# Vaibhav_Data_logger.net
KiCad netlist of a schematic drawn in EAGLE
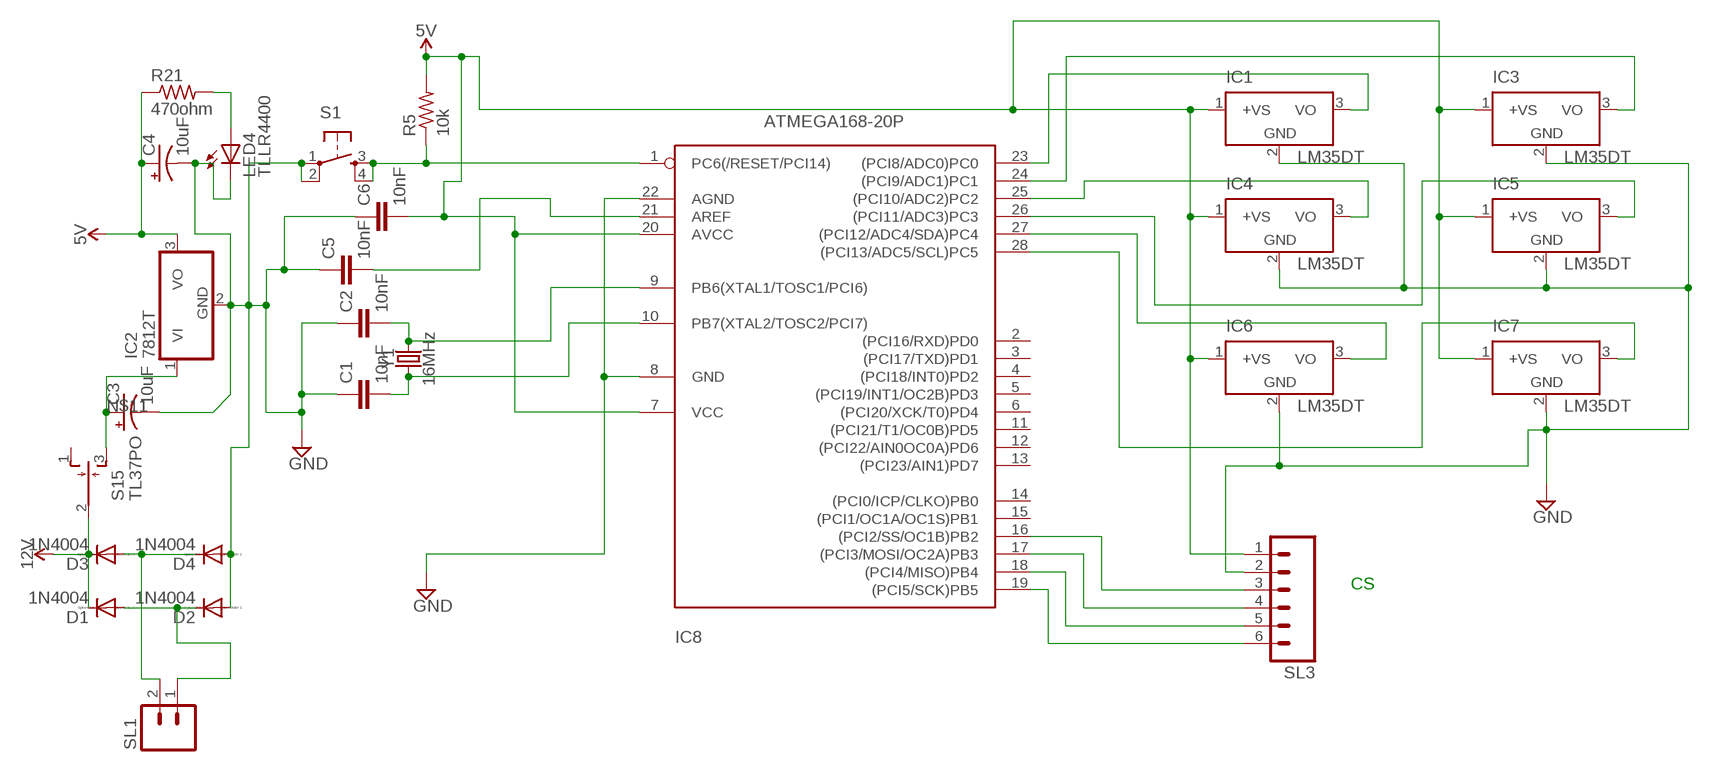
[diagram p0: schematic, sheet 1]

(export (version "E")
  (design (tool "Eeschema 10.0.6"))
  (components
    (comp (ref "C1")
      (value "10nF")
      (footprint "eagle-import:CAP-PTH-10MM")
      (libsource (lib "eagle-import") (part "10NF-PTH-10MM-10000V-1-%"))
    )
    (comp (ref "C2")
      (value "10nF")
      (footprint "eagle-import:CAP-PTH-10MM")
      (libsource (lib "eagle-import") (part "10NF-PTH-10MM-10000V-1-%"))
    )
    (comp (ref "C3")
      (value "10uF")
      (footprint "eagle-import:CPOL-RADIAL-2.5MM-5MM-KIT")
      (libsource (lib "eagle-import") (part "10UF-POLAR-RADIAL-2.5MM-KIT-25V-20%"))
    )
    (comp (ref "C4")
      (value "10uF")
      (footprint "eagle-import:CPOL-RADIAL-2.5MM-5MM-KIT")
      (libsource (lib "eagle-import") (part "10UF-POLAR-RADIAL-2.5MM-KIT-25V-20%"))
    )
    (comp (ref "C5")
      (value "10nF")
      (footprint "eagle-import:CAP-PTH-10MM")
      (libsource (lib "eagle-import") (part "10NF-PTH-10MM-10000V-1-%"))
    )
    (comp (ref "C6")
      (value "10nF")
      (footprint "eagle-import:CAP-PTH-10MM")
      (libsource (lib "eagle-import") (part "10NF-PTH-10MM-10000V-1-%"))
    )
    (comp (ref "D1")
      (value "1N4004")
      (footprint "eagle-import:DO41-10")
      (libsource (lib "eagle-import") (part "1N4004"))
    )
    (comp (ref "D2")
      (value "1N4004")
      (footprint "eagle-import:DO41-10")
      (libsource (lib "eagle-import") (part "1N4004"))
    )
    (comp (ref "D3")
      (value "1N4004")
      (footprint "eagle-import:DO41-10")
      (libsource (lib "eagle-import") (part "1N4004"))
    )
    (comp (ref "D4")
      (value "1N4004")
      (footprint "eagle-import:DO41-10")
      (libsource (lib "eagle-import") (part "1N4004"))
    )
    (comp (ref "IC1")
      (value "LM35DT")
      (footprint "eagle-import:TO220V")
      (libsource (lib "eagle-import") (part "LM35DT"))
    )
    (comp (ref "IC2")
      (value "7812T")
      (footprint "eagle-import:TO220H")
      (libsource (lib "eagle-import") (part "78T12"))
    )
    (comp (ref "IC3")
      (value "LM35DT")
      (footprint "eagle-import:TO220V")
      (libsource (lib "eagle-import") (part "LM35DT"))
    )
    (comp (ref "IC4")
      (value "LM35DT")
      (footprint "eagle-import:TO220V")
      (libsource (lib "eagle-import") (part "LM35DT"))
    )
    (comp (ref "IC5")
      (value "LM35DT")
      (footprint "eagle-import:TO220V")
      (libsource (lib "eagle-import") (part "LM35DT"))
    )
    (comp (ref "IC6")
      (value "LM35DT")
      (footprint "eagle-import:TO220V")
      (libsource (lib "eagle-import") (part "LM35DT"))
    )
    (comp (ref "IC7")
      (value "LM35DT")
      (footprint "eagle-import:TO220V")
      (libsource (lib "eagle-import") (part "LM35DT"))
    )
    (comp (ref "IC8")
      (value "ATMEGA168-20P")
      (footprint "eagle-import:DIL28-3")
      (libsource (lib "eagle-import") (part "ATMEGA168P-20"))
    )
    (comp (ref "LED4")
      (value "TLLR4400")
      (footprint "eagle-import:LED3MM")
      (fields (field (name "MF") "VISHAY SEMICONDUCTOR"))
      (libsource (lib "eagle-import") (part "TLLR4400"))
    )
    (comp (ref "R5")
      (value "10k")
      (footprint "eagle-import:0207_12")
      (libsource (lib "eagle-import") (part "R-US_0207/12"))
    )
    (comp (ref "R21")
      (value "470ohm")
      (footprint "eagle-import:0207_12")
      (libsource (lib "eagle-import") (part "R-US_0207/12"))
    )
    (comp (ref "S1")
      (value "TAC_SWITCHPTH")
      (footprint "eagle-import:TACTILE-PTH")
      (libsource (lib "eagle-import") (part "TAC_SWITCHPTH"))
    )
    (comp (ref "S15")
      (value "TL37PO")
      (footprint "eagle-import:TL3XPO")
      (libsource (lib "eagle-import") (part "TL37PO"))
    )
    (comp (ref "SL1")
      (value "MA02")
      (footprint "eagle-import:02PA")
      (libsource (lib "eagle-import") (part "MA02"))
    )
    (comp (ref "SL3")
      (value "MA06")
      (footprint "eagle-import:06PA")
      (libsource (lib "eagle-import") (part "MA06"))
    )
    (comp (ref "Y1")
      (value "16MHz")
      (footprint "eagle-import:HC49US")
      (libsource (lib "eagle-import") (part "CRYSTAL-16MHZPTH-HC49US"))
    )
  )
  (nets
    (net (code "1") (name "/N$11") (class "Default")
      (node (ref "C3") (pin "1") (pinfunction "+_1") (pintype "passive"))
      (node (ref "IC2") (pin "1") (pinfunction "VI_1") (pintype "input"))
      (node (ref "S15") (pin "3") (pinfunction "S_3") (pintype "passive"))
    )
    (net (code "2") (name "5V") (class "Default")
      (node (ref "C4") (pin "1") (pinfunction "+_1") (pintype "passive"))
      (node (ref "C6") (pin "2") (pinfunction "2_2") (pintype "passive"))
      (node (ref "IC1") (pin "1") (pinfunction "+VS_1") (pintype "input"))
      (node (ref "IC2") (pin "3") (pinfunction "VO_3") (pintype "passive"))
      (node (ref "IC3") (pin "1") (pinfunction "+VS_1") (pintype "input"))
      (node (ref "IC4") (pin "1") (pinfunction "+VS_1") (pintype "input"))
      (node (ref "IC5") (pin "1") (pinfunction "+VS_1") (pintype "input"))
      (node (ref "IC6") (pin "1") (pinfunction "+VS_1") (pintype "input"))
      (node (ref "IC7") (pin "1") (pinfunction "+VS_1") (pintype "input"))
      (node (ref "IC8") (pin "20") (pinfunction "AVCC_20") (pintype "bidirectional"))
      (node (ref "IC8") (pin "7") (pinfunction "VCC_7") (pintype "bidirectional"))
      (node (ref "R21") (pin "1") (pinfunction "1_1") (pintype "passive"))
      (node (ref "R5") (pin "2") (pinfunction "2_2") (pintype "passive"))
      (node (ref "SL3") (pin "1") (pinfunction "1_1") (pintype "passive"))
    )
    (net (code "3") (name "12V") (class "Default")
      (node (ref "D1") (pin "C") (pinfunction "C_C") (pintype "passive"))
      (node (ref "D3") (pin "C") (pinfunction "C_C") (pintype "passive"))
      (node (ref "S15") (pin "2") (pinfunction "P_2") (pintype "passive"))
    )
    (net (code "4") (name "GND") (class "Default")
      (node (ref "C1") (pin "1") (pinfunction "1_1") (pintype "passive"))
      (node (ref "C2") (pin "1") (pinfunction "1_1") (pintype "passive"))
      (node (ref "C3") (pin "2") (pinfunction "-_2") (pintype "passive"))
      (node (ref "C4") (pin "2") (pinfunction "-_2") (pintype "passive"))
      (node (ref "C5") (pin "1") (pinfunction "1_1") (pintype "passive"))
      (node (ref "C6") (pin "1") (pinfunction "1_1") (pintype "passive"))
      (node (ref "D2") (pin "A") (pinfunction "A_A") (pintype "passive"))
      (node (ref "D4") (pin "A") (pinfunction "A_A") (pintype "passive"))
      (node (ref "IC1") (pin "2") (pinfunction "GND_2") (pintype "power_in"))
      (node (ref "IC2") (pin "2") (pinfunction "GND_2") (pintype "passive"))
      (node (ref "IC3") (pin "2") (pinfunction "GND_2") (pintype "power_in"))
      (node (ref "IC4") (pin "2") (pinfunction "GND_2") (pintype "power_in"))
      (node (ref "IC5") (pin "2") (pinfunction "GND_2") (pintype "power_in"))
      (node (ref "IC6") (pin "2") (pinfunction "GND_2") (pintype "power_in"))
      (node (ref "IC7") (pin "2") (pinfunction "GND_2") (pintype "power_in"))
      (node (ref "IC8") (pin "22") (pinfunction "AGND_22") (pintype "bidirectional"))
      (node (ref "IC8") (pin "8") (pinfunction "GND_8") (pintype "bidirectional"))
      (node (ref "LED4") (pin "K") (pinfunction "C_K") (pintype "passive"))
      (node (ref "S1") (pin "1") (pinfunction "1_1") (pintype "passive"))
      (node (ref "S1") (pin "2") (pinfunction "2_2") (pintype "passive"))
      (node (ref "SL3") (pin "2") (pinfunction "2_2") (pintype "passive"))
    )
    (net (code "5") (name "Net-(D1-PadA)") (class "Default")
      (node (ref "D1") (pin "A") (pinfunction "A_A") (pintype "passive"))
      (node (ref "D2") (pin "C") (pinfunction "C_C") (pintype "passive"))
      (node (ref "SL1") (pin "1") (pinfunction "1_1") (pintype "passive"))
    )
    (net (code "6") (name "Net-(D3-PadA)") (class "Default")
      (node (ref "D3") (pin "A") (pinfunction "A_A") (pintype "passive"))
      (node (ref "D4") (pin "C") (pinfunction "C_C") (pintype "passive"))
      (node (ref "SL1") (pin "2") (pinfunction "2_2") (pintype "passive"))
    )
    (net (code "7") (name "Net-(IC1-VO)") (class "Default")
      (node (ref "IC1") (pin "3") (pinfunction "VO_3") (pintype "input"))
      (node (ref "IC8") (pin "23") (pinfunction "(PCI8/ADC0)PC0_23") (pintype "bidirectional"))
    )
    (net (code "8") (name "Net-(IC3-VO)") (class "Default")
      (node (ref "IC3") (pin "3") (pinfunction "VO_3") (pintype "input"))
      (node (ref "IC8") (pin "24") (pinfunction "(PCI9/ADC1)PC1_24") (pintype "bidirectional"))
    )
    (net (code "9") (name "Net-(IC4-VO)") (class "Default")
      (node (ref "IC4") (pin "3") (pinfunction "VO_3") (pintype "input"))
      (node (ref "IC8") (pin "25") (pinfunction "(PCI10/ADC2)PC2_25") (pintype "bidirectional"))
    )
    (net (code "10") (name "Net-(IC5-VO)") (class "Default")
      (node (ref "IC5") (pin "3") (pinfunction "VO_3") (pintype "input"))
      (node (ref "IC8") (pin "26") (pinfunction "(PCI11/ADC3)PC3_26") (pintype "bidirectional"))
    )
    (net (code "11") (name "Net-(IC6-VO)") (class "Default")
      (node (ref "IC6") (pin "3") (pinfunction "VO_3") (pintype "input"))
      (node (ref "IC8") (pin "27") (pinfunction "(PCI12/ADC4/SDA)PC4_27") (pintype "bidirectional"))
    )
    (net (code "12") (name "Net-(IC7-VO)") (class "Default")
      (node (ref "IC7") (pin "3") (pinfunction "VO_3") (pintype "input"))
      (node (ref "IC8") (pin "28") (pinfunction "(PCI13/ADC5/SCL)PC5_28") (pintype "bidirectional"))
    )
    (net (code "13") (name "Net-(IC8-(PCI2{slash}SS{slash}OC1B)PB2)") (class "Default")
      (node (ref "IC8") (pin "16") (pinfunction "(PCI2/SS/OC1B)PB2_16") (pintype "bidirectional"))
      (node (ref "SL3") (pin "3") (pinfunction "3_3") (pintype "passive"))
    )
    (net (code "14") (name "Net-(IC8-(PCI3{slash}MOSI{slash}OC2A)PB3)") (class "Default")
      (node (ref "IC8") (pin "17") (pinfunction "(PCI3/MOSI/OC2A)PB3_17") (pintype "bidirectional"))
      (node (ref "SL3") (pin "4") (pinfunction "4_4") (pintype "passive"))
    )
    (net (code "15") (name "Net-(IC8-(PCI4{slash}MISO)PB4)") (class "Default")
      (node (ref "IC8") (pin "18") (pinfunction "(PCI4/MISO)PB4_18") (pintype "bidirectional"))
      (node (ref "SL3") (pin "5") (pinfunction "5_5") (pintype "passive"))
    )
    (net (code "16") (name "Net-(IC8-(PCI5{slash}SCK)PB5)") (class "Default")
      (node (ref "IC8") (pin "19") (pinfunction "(PCI5/SCK)PB5_19") (pintype "bidirectional"))
      (node (ref "SL3") (pin "6") (pinfunction "6_6") (pintype "passive"))
    )
    (net (code "17") (name "Net-(IC8-AREF)") (class "Default")
      (node (ref "C5") (pin "2") (pinfunction "2_2") (pintype "passive"))
      (node (ref "IC8") (pin "21") (pinfunction "AREF_21") (pintype "bidirectional"))
    )
    (net (code "18") (name "Net-(IC8-PB6(XTAL1{slash}TOSC1{slash}PCI6))") (class "Default")
      (node (ref "C2") (pin "2") (pinfunction "2_2") (pintype "passive"))
      (node (ref "IC8") (pin "9") (pinfunction "PB6(XTAL1/TOSC1/PCI6)_9") (pintype "bidirectional"))
      (node (ref "Y1") (pin "2") (pinfunction "2_2") (pintype "passive"))
    )
    (net (code "19") (name "Net-(IC8-PB7(XTAL2{slash}TOSC2{slash}PCI7))") (class "Default")
      (node (ref "C1") (pin "2") (pinfunction "2_2") (pintype "passive"))
      (node (ref "IC8") (pin "10") (pinfunction "PB7(XTAL2/TOSC2/PCI7)_10") (pintype "bidirectional"))
      (node (ref "Y1") (pin "1") (pinfunction "1_1") (pintype "passive"))
    )
    (net (code "20") (name "Net-(IC8-PC6({slash}RESET{slash}PCI14))") (class "Default")
      (node (ref "IC8") (pin "1") (pinfunction "PC6(/RESET/PCI14)_1") (pintype "bidirectional"))
      (node (ref "R5") (pin "1") (pinfunction "1_1") (pintype "passive"))
      (node (ref "S1") (pin "3") (pinfunction "3_3") (pintype "passive"))
      (node (ref "S1") (pin "4") (pinfunction "4_4") (pintype "passive"))
    )
    (net (code "21") (name "Net-(LED4-PadA)") (class "Default")
      (node (ref "LED4") (pin "A") (pinfunction "A_A") (pintype "passive"))
      (node (ref "R21") (pin "2") (pinfunction "2_2") (pintype "passive"))
    )
    (net (code "22") (name "unconnected-(IC8-(PCI0{slash}ICP{slash}CLKO)PB0-Pad14)") (class "Default")
      (node (ref "IC8") (pin "14") (pinfunction "(PCI0/ICP/CLKO)PB0_14") (pintype "bidirectional"))
    )
    (net (code "23") (name "unconnected-(IC8-(PCI1{slash}OC1A{slash}OC1S)PB1-Pad15)") (class "Default")
      (node (ref "IC8") (pin "15") (pinfunction "(PCI1/OC1A/OC1S)PB1_15") (pintype "bidirectional"))
    )
    (net (code "24") (name "unconnected-(IC8-(PCI16{slash}RXD)PD0-Pad2)") (class "Default")
      (node (ref "IC8") (pin "2") (pinfunction "(PCI16/RXD)PD0_2") (pintype "bidirectional"))
    )
    (net (code "25") (name "unconnected-(IC8-(PCI17{slash}TXD)PD1-Pad3)") (class "Default")
      (node (ref "IC8") (pin "3") (pinfunction "(PCI17/TXD)PD1_3") (pintype "bidirectional"))
    )
    (net (code "26") (name "unconnected-(IC8-(PCI18{slash}INT0)PD2-Pad4)") (class "Default")
      (node (ref "IC8") (pin "4") (pinfunction "(PCI18/INT0)PD2_4") (pintype "bidirectional"))
    )
    (net (code "27") (name "unconnected-(IC8-(PCI19{slash}INT1{slash}OC2B)PD3-Pad5)") (class "Default")
      (node (ref "IC8") (pin "5") (pinfunction "(PCI19/INT1/OC2B)PD3_5") (pintype "bidirectional"))
    )
    (net (code "28") (name "unconnected-(IC8-(PCI20{slash}XCK{slash}T0)PD4-Pad6)") (class "Default")
      (node (ref "IC8") (pin "6") (pinfunction "(PCI20/XCK/T0)PD4_6") (pintype "bidirectional"))
    )
    (net (code "29") (name "unconnected-(IC8-(PCI21{slash}T1{slash}OC0B)PD5-Pad11)") (class "Default")
      (node (ref "IC8") (pin "11") (pinfunction "(PCI21/T1/OC0B)PD5_11") (pintype "bidirectional"))
    )
    (net (code "30") (name "unconnected-(IC8-(PCI22{slash}AIN0OC0A)PD6-Pad12)") (class "Default")
      (node (ref "IC8") (pin "12") (pinfunction "(PCI22/AIN0OC0A)PD6_12") (pintype "bidirectional"))
    )
    (net (code "31") (name "unconnected-(IC8-(PCI23{slash}AIN1)PD7-Pad13)") (class "Default")
      (node (ref "IC8") (pin "13") (pinfunction "(PCI23/AIN1)PD7_13") (pintype "bidirectional"))
    )
    (net (code "32") (name "unconnected-(S15-O-Pad1)") (class "Default")
      (node (ref "S15") (pin "1") (pinfunction "O_1") (pintype "passive"))
    )
  )
)
